# bt4_0_shield.net
KiCad netlist of a schematic drawn in EAGLE
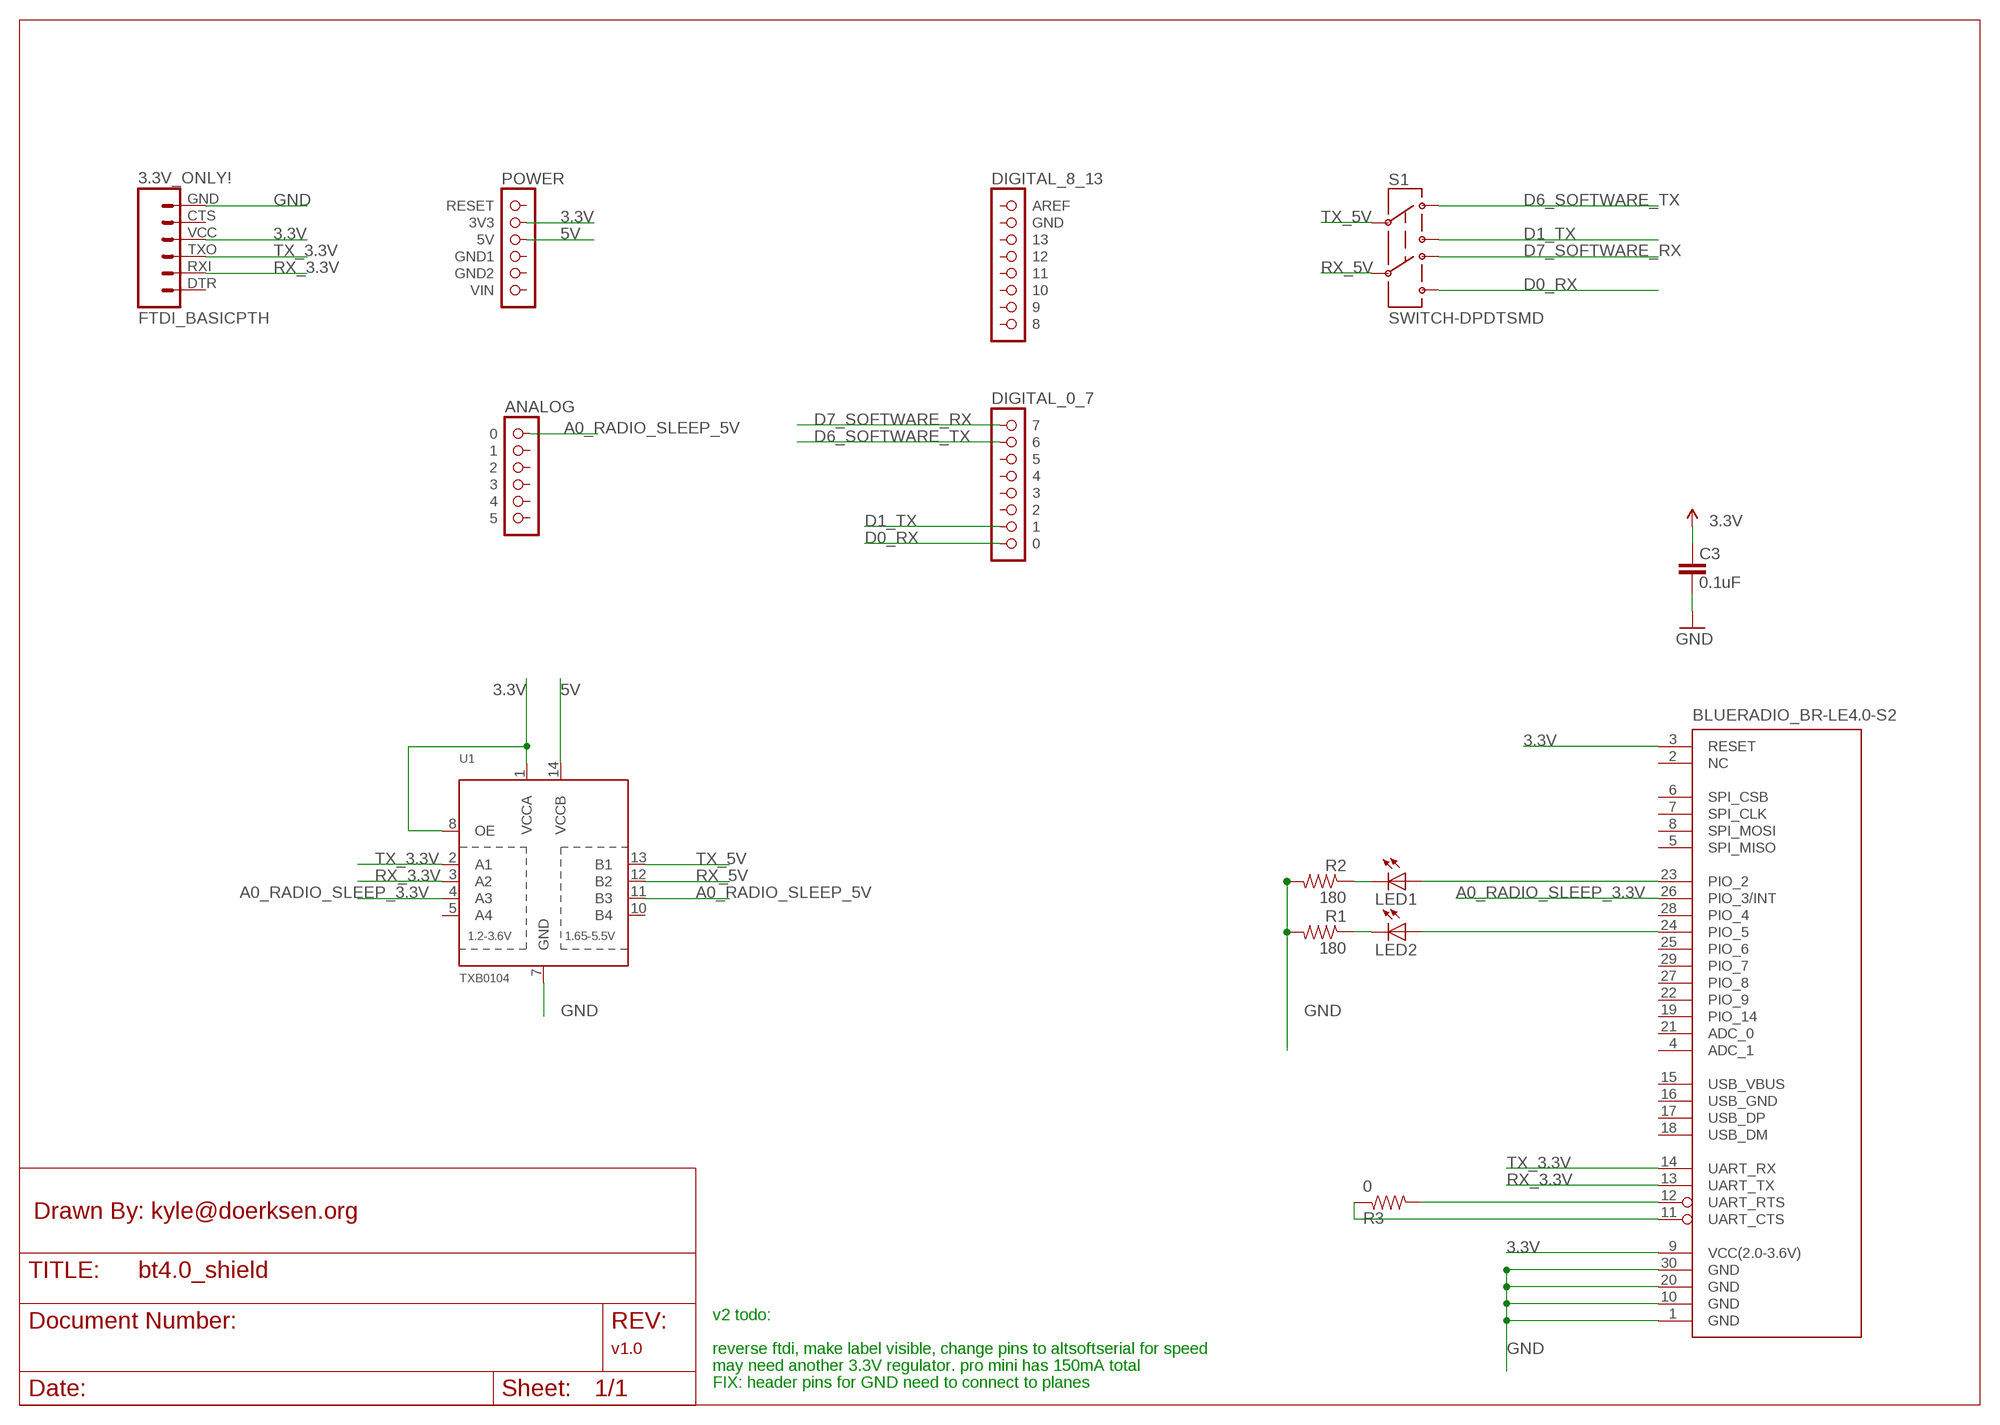
[diagram p0: schematic, sheet 1]

(export (version "E")
  (design (tool "Eeschema 10.0.6"))
  (components
    (comp (ref "3.3V_ONLY!")
      (value "FTDI_BASICPTH")
      (footprint "eagle-import:FTDI_BASIC")
      (libsource (lib "eagle-import") (part "FTDI_BASICPTH"))
    )
    (comp (ref "BLUERADIO_BR-LE4.0-S2")
      (value "BLUERADIO_BR-LE4.0-S2")
      (footprint "eagle-import:BLUERADIO_BR-LE4.0-S2")
      (libsource (lib "eagle-import") (part "BLUERADIO_BR-LE4.0-S2"))
    )
    (comp (ref "C3")
      (value "0.1uF")
      (footprint "eagle-import:0402-CAP")
      (libsource (lib "eagle-import") (part "CAP0402-CAP"))
    )
    (comp (ref "LED1")
      (value "LED0603")
      (footprint "eagle-import:LED-0603")
      (libsource (lib "eagle-import") (part "LED0603"))
    )
    (comp (ref "LED2")
      (value "LED0603")
      (footprint "eagle-import:LED-0603")
      (libsource (lib "eagle-import") (part "LED0603"))
    )
    (comp (ref "R1")
      (value "180")
      (footprint "eagle-import:0402-RES")
      (libsource (lib "eagle-import") (part "RESISTOR0402-RES"))
    )
    (comp (ref "R2")
      (value "180")
      (footprint "eagle-import:0402-RES")
      (libsource (lib "eagle-import") (part "RESISTOR0402-RES"))
    )
    (comp (ref "R3")
      (value "0")
      (footprint "eagle-import:0402-RES")
      (libsource (lib "eagle-import") (part "RESISTOR0402-RES"))
    )
    (comp (ref "S1")
      (value "SWITCH-DPDTSMD")
      (footprint "eagle-import:AYZ0202")
      (libsource (lib "eagle-import") (part "SWITCH-DPDTSMD"))
    )
    (comp (ref "U$1")
      (value "POWER")
      (footprint "eagle-import:1X06")
      (libsource (lib "eagle-import") (part "POWER"))
    )
    (comp (ref "U$2")
      (value "ANALOG")
      (footprint "eagle-import:1X06")
      (libsource (lib "eagle-import") (part "ANALOG"))
    )
    (comp (ref "U$3")
      (value "DIGITAL_0_7")
      (footprint "eagle-import:1X08")
      (libsource (lib "eagle-import") (part "DIGITAL_0_7"))
    )
    (comp (ref "U$4")
      (value "DIGITAL_8_13")
      (footprint "eagle-import:1X08")
      (libsource (lib "eagle-import") (part "DIGITAL_8_13"))
    )
    (comp (ref "U1")
      (value "TXB0104")
      (footprint "eagle-import:SO14")
      (libsource (lib "eagle-import") (part "TXB0104PWRSOIC14"))
    )
  )
  (nets
    (net (code "1") (name "/5V") (class "Default")
      (node (ref "U$1") (pin "3") (pinfunction "5V_3") (pintype "passive"))
      (node (ref "U1") (pin "14") (pinfunction "VCCB_14") (pintype "bidirectional"))
    )
    (net (code "2") (name "/A0_RADIO_SLEEP_3.3V") (class "Default")
      (node (ref "BLUERADIO_BR-LE4.0-S2") (pin "26") (pinfunction "PIO_3/INT_26") (pintype "bidirectional"))
      (node (ref "U1") (pin "4") (pinfunction "A3_4") (pintype "bidirectional"))
    )
    (net (code "3") (name "/A0_RADIO_SLEEP_5V") (class "Default")
      (node (ref "U$2") (pin "1") (pinfunction "0_1") (pintype "passive"))
      (node (ref "U1") (pin "11") (pinfunction "B3_11") (pintype "bidirectional"))
    )
    (net (code "4") (name "/D0_RX") (class "Default")
      (node (ref "S1") (pin "6") (pinfunction "6_6") (pintype "bidirectional"))
      (node (ref "U$3") (pin "8") (pinfunction "0_8") (pintype "passive"))
    )
    (net (code "5") (name "/D1_TX") (class "Default")
      (node (ref "S1") (pin "3") (pinfunction "3_3") (pintype "bidirectional"))
      (node (ref "U$3") (pin "7") (pinfunction "1_7") (pintype "passive"))
    )
    (net (code "6") (name "/D6_SOFTWARE_TX") (class "Default")
      (node (ref "S1") (pin "1") (pinfunction "1_1") (pintype "bidirectional"))
      (node (ref "U$3") (pin "2") (pinfunction "6_2") (pintype "passive"))
    )
    (net (code "7") (name "/D7_SOFTWARE_RX") (class "Default")
      (node (ref "S1") (pin "4") (pinfunction "4_4") (pintype "bidirectional"))
      (node (ref "U$3") (pin "1") (pinfunction "7_1") (pintype "passive"))
    )
    (net (code "8") (name "/RX_3.3V") (class "Default")
      (node (ref "3.3V_ONLY!") (pin "RXI") (pinfunction "2_RXI") (pintype "passive"))
      (node (ref "BLUERADIO_BR-LE4.0-S2") (pin "13") (pinfunction "UART_TX_13") (pintype "output"))
      (node (ref "U1") (pin "3") (pinfunction "A2_3") (pintype "bidirectional"))
    )
    (net (code "9") (name "/RX_5V") (class "Default")
      (node (ref "S1") (pin "5") (pinfunction "5_5") (pintype "bidirectional"))
      (node (ref "U1") (pin "12") (pinfunction "B2_12") (pintype "bidirectional"))
    )
    (net (code "10") (name "/TX_3.3V") (class "Default")
      (node (ref "3.3V_ONLY!") (pin "TXO") (pinfunction "3_TXO") (pintype "passive"))
      (node (ref "BLUERADIO_BR-LE4.0-S2") (pin "14") (pinfunction "UART_RX_14") (pintype "input"))
      (node (ref "U1") (pin "2") (pinfunction "A1_2") (pintype "bidirectional"))
    )
    (net (code "11") (name "/TX_5V") (class "Default")
      (node (ref "S1") (pin "2") (pinfunction "2_2") (pintype "bidirectional"))
      (node (ref "U1") (pin "13") (pinfunction "B1_13") (pintype "bidirectional"))
    )
    (net (code "12") (name "GND") (class "Default")
      (node (ref "3.3V_ONLY!") (pin "GND") (pinfunction "6_GND") (pintype "passive"))
      (node (ref "BLUERADIO_BR-LE4.0-S2") (pin "1") (pinfunction "GND_1") (pintype "power_in"))
      (node (ref "BLUERADIO_BR-LE4.0-S2") (pin "10") (pinfunction "GND_10") (pintype "power_in"))
      (node (ref "BLUERADIO_BR-LE4.0-S2") (pin "20") (pinfunction "GND_20") (pintype "power_in"))
      (node (ref "BLUERADIO_BR-LE4.0-S2") (pin "30") (pinfunction "GND_30") (pintype "power_in"))
      (node (ref "C3") (pin "1") (pinfunction "1_1") (pintype "passive"))
      (node (ref "R1") (pin "2") (pinfunction "2_2") (pintype "passive"))
      (node (ref "R2") (pin "2") (pinfunction "2_2") (pintype "passive"))
      (node (ref "U1") (pin "7") (pinfunction "GND_7") (pintype "bidirectional"))
    )
    (net (code "13") (name "Net-(BLUERADIO_BR-LE4.0-S2-PIO_2)") (class "Default")
      (node (ref "BLUERADIO_BR-LE4.0-S2") (pin "23") (pinfunction "PIO_2_23") (pintype "bidirectional"))
      (node (ref "LED1") (pin "A") (pinfunction "A_A") (pintype "passive"))
    )
    (net (code "14") (name "Net-(BLUERADIO_BR-LE4.0-S2-PIO_5)") (class "Default")
      (node (ref "BLUERADIO_BR-LE4.0-S2") (pin "24") (pinfunction "PIO_5_24") (pintype "bidirectional"))
      (node (ref "LED2") (pin "A") (pinfunction "A_A") (pintype "passive"))
    )
    (net (code "15") (name "Net-(BLUERADIO_BR-LE4.0-S2-UART_CTS)") (class "Default")
      (node (ref "BLUERADIO_BR-LE4.0-S2") (pin "11") (pinfunction "UART_CTS_11") (pintype "input"))
      (node (ref "R3") (pin "1") (pinfunction "1_1") (pintype "passive"))
    )
    (net (code "16") (name "Net-(BLUERADIO_BR-LE4.0-S2-UART_RTS)") (class "Default")
      (node (ref "BLUERADIO_BR-LE4.0-S2") (pin "12") (pinfunction "UART_RTS_12") (pintype "output"))
      (node (ref "R3") (pin "2") (pinfunction "2_2") (pintype "passive"))
    )
    (net (code "17") (name "Net-(LED1-PadC)") (class "Default")
      (node (ref "LED1") (pin "C") (pinfunction "C_C") (pintype "passive"))
      (node (ref "R2") (pin "1") (pinfunction "1_1") (pintype "passive"))
    )
    (net (code "18") (name "Net-(LED2-PadC)") (class "Default")
      (node (ref "LED2") (pin "C") (pinfunction "C_C") (pintype "passive"))
      (node (ref "R1") (pin "1") (pinfunction "1_1") (pintype "passive"))
    )
    (net (code "19") (name "VCC") (class "Default")
      (node (ref "3.3V_ONLY!") (pin "VCC") (pinfunction "4_VCC") (pintype "passive"))
      (node (ref "BLUERADIO_BR-LE4.0-S2") (pin "3") (pinfunction "RESET_3") (pintype "input"))
      (node (ref "BLUERADIO_BR-LE4.0-S2") (pin "9") (pinfunction "VCC(2.0-3.6V)_9") (pintype "power_in"))
      (node (ref "C3") (pin "2") (pinfunction "2_2") (pintype "passive"))
      (node (ref "U$1") (pin "2") (pinfunction "3V3_2") (pintype "passive"))
      (node (ref "U1") (pin "1") (pinfunction "VCCA_1") (pintype "bidirectional"))
      (node (ref "U1") (pin "8") (pinfunction "OE_8") (pintype "bidirectional"))
    )
    (net (code "20") (name "unconnected-(3.3V_ONLY!-1-PadDTR)") (class "Default")
      (node (ref "3.3V_ONLY!") (pin "DTR") (pinfunction "1_DTR") (pintype "passive"))
    )
    (net (code "21") (name "unconnected-(3.3V_ONLY!-5-PadCTS)") (class "Default")
      (node (ref "3.3V_ONLY!") (pin "CTS") (pinfunction "5_CTS") (pintype "passive"))
    )
    (net (code "22") (name "unconnected-(BLUERADIO_BR-LE4.0-S2-ADC_0-Pad21)") (class "Default")
      (node (ref "BLUERADIO_BR-LE4.0-S2") (pin "21") (pinfunction "ADC_0_21") (pintype "input"))
    )
    (net (code "23") (name "unconnected-(BLUERADIO_BR-LE4.0-S2-ADC_1-Pad4)") (class "Default")
      (node (ref "BLUERADIO_BR-LE4.0-S2") (pin "4") (pinfunction "ADC_1_4") (pintype "input"))
    )
    (net (code "24") (name "unconnected-(BLUERADIO_BR-LE4.0-S2-NC-Pad2)") (class "Default")
      (node (ref "BLUERADIO_BR-LE4.0-S2") (pin "2") (pinfunction "NC_2") (pintype "no_connect"))
    )
    (net (code "25") (name "unconnected-(BLUERADIO_BR-LE4.0-S2-PIO_4-Pad28)") (class "Default")
      (node (ref "BLUERADIO_BR-LE4.0-S2") (pin "28") (pinfunction "PIO_4_28") (pintype "bidirectional"))
    )
    (net (code "26") (name "unconnected-(BLUERADIO_BR-LE4.0-S2-PIO_6-Pad25)") (class "Default")
      (node (ref "BLUERADIO_BR-LE4.0-S2") (pin "25") (pinfunction "PIO_6_25") (pintype "bidirectional"))
    )
    (net (code "27") (name "unconnected-(BLUERADIO_BR-LE4.0-S2-PIO_7-Pad29)") (class "Default")
      (node (ref "BLUERADIO_BR-LE4.0-S2") (pin "29") (pinfunction "PIO_7_29") (pintype "bidirectional"))
    )
    (net (code "28") (name "unconnected-(BLUERADIO_BR-LE4.0-S2-PIO_8-Pad27)") (class "Default")
      (node (ref "BLUERADIO_BR-LE4.0-S2") (pin "27") (pinfunction "PIO_8_27") (pintype "bidirectional"))
    )
    (net (code "29") (name "unconnected-(BLUERADIO_BR-LE4.0-S2-PIO_9-Pad22)") (class "Default")
      (node (ref "BLUERADIO_BR-LE4.0-S2") (pin "22") (pinfunction "PIO_9_22") (pintype "bidirectional"))
    )
    (net (code "30") (name "unconnected-(BLUERADIO_BR-LE4.0-S2-PIO_14-Pad19)") (class "Default")
      (node (ref "BLUERADIO_BR-LE4.0-S2") (pin "19") (pinfunction "PIO_14_19") (pintype "bidirectional"))
    )
    (net (code "31") (name "unconnected-(BLUERADIO_BR-LE4.0-S2-SPI_CLK-Pad7)") (class "Default")
      (node (ref "BLUERADIO_BR-LE4.0-S2") (pin "7") (pinfunction "SPI_CLK_7") (pintype "bidirectional"))
    )
    (net (code "32") (name "unconnected-(BLUERADIO_BR-LE4.0-S2-SPI_CSB-Pad6)") (class "Default")
      (node (ref "BLUERADIO_BR-LE4.0-S2") (pin "6") (pinfunction "SPI_CSB_6") (pintype "bidirectional"))
    )
    (net (code "33") (name "unconnected-(BLUERADIO_BR-LE4.0-S2-SPI_MISO-Pad5)") (class "Default")
      (node (ref "BLUERADIO_BR-LE4.0-S2") (pin "5") (pinfunction "SPI_MISO_5") (pintype "bidirectional"))
    )
    (net (code "34") (name "unconnected-(BLUERADIO_BR-LE4.0-S2-SPI_MOSI-Pad8)") (class "Default")
      (node (ref "BLUERADIO_BR-LE4.0-S2") (pin "8") (pinfunction "SPI_MOSI_8") (pintype "bidirectional"))
    )
    (net (code "35") (name "unconnected-(BLUERADIO_BR-LE4.0-S2-USB_DM-Pad18)") (class "Default")
      (node (ref "BLUERADIO_BR-LE4.0-S2") (pin "18") (pinfunction "USB_DM_18") (pintype "bidirectional"))
    )
    (net (code "36") (name "unconnected-(BLUERADIO_BR-LE4.0-S2-USB_DP-Pad17)") (class "Default")
      (node (ref "BLUERADIO_BR-LE4.0-S2") (pin "17") (pinfunction "USB_DP_17") (pintype "bidirectional"))
    )
    (net (code "37") (name "unconnected-(BLUERADIO_BR-LE4.0-S2-USB_GND-Pad16)") (class "Default")
      (node (ref "BLUERADIO_BR-LE4.0-S2") (pin "16") (pinfunction "USB_GND_16") (pintype "bidirectional"))
    )
    (net (code "38") (name "unconnected-(BLUERADIO_BR-LE4.0-S2-USB_VBUS-Pad15)") (class "Default")
      (node (ref "BLUERADIO_BR-LE4.0-S2") (pin "15") (pinfunction "USB_VBUS_15") (pintype "bidirectional"))
    )
    (net (code "39") (name "unconnected-(U$1-GND1-Pad4)") (class "Default")
      (node (ref "U$1") (pin "4") (pinfunction "GND1_4") (pintype "passive"))
    )
    (net (code "40") (name "unconnected-(U$1-GND2-Pad5)") (class "Default")
      (node (ref "U$1") (pin "5") (pinfunction "GND2_5") (pintype "passive"))
    )
    (net (code "41") (name "unconnected-(U$1-RESET-Pad1)") (class "Default")
      (node (ref "U$1") (pin "1") (pinfunction "RESET_1") (pintype "passive"))
    )
    (net (code "42") (name "unconnected-(U$1-VIN-Pad6)") (class "Default")
      (node (ref "U$1") (pin "6") (pinfunction "VIN_6") (pintype "passive"))
    )
    (net (code "43") (name "unconnected-(U$2-1-Pad2)") (class "Default")
      (node (ref "U$2") (pin "2") (pinfunction "1_2") (pintype "passive"))
    )
    (net (code "44") (name "unconnected-(U$2-2-Pad3)") (class "Default")
      (node (ref "U$2") (pin "3") (pinfunction "2_3") (pintype "passive"))
    )
    (net (code "45") (name "unconnected-(U$2-3-Pad4)") (class "Default")
      (node (ref "U$2") (pin "4") (pinfunction "3_4") (pintype "passive"))
    )
    (net (code "46") (name "unconnected-(U$2-4-Pad5)") (class "Default")
      (node (ref "U$2") (pin "5") (pinfunction "4_5") (pintype "passive"))
    )
    (net (code "47") (name "unconnected-(U$2-5-Pad6)") (class "Default")
      (node (ref "U$2") (pin "6") (pinfunction "5_6") (pintype "passive"))
    )
    (net (code "48") (name "unconnected-(U$3-2-Pad6)") (class "Default")
      (node (ref "U$3") (pin "6") (pinfunction "2_6") (pintype "passive"))
    )
    (net (code "49") (name "unconnected-(U$3-3-Pad5)") (class "Default")
      (node (ref "U$3") (pin "5") (pinfunction "3_5") (pintype "passive"))
    )
    (net (code "50") (name "unconnected-(U$3-5-Pad3)") (class "Default")
      (node (ref "U$3") (pin "3") (pinfunction "5_3") (pintype "passive"))
    )
    (net (code "51") (name "unconnected-(U$3-Pad4)") (class "Default")
      (node (ref "U$3") (pin "4") (pinfunction "4_4") (pintype "passive"))
    )
    (net (code "52") (name "unconnected-(U$4-9-Pad7)") (class "Default")
      (node (ref "U$4") (pin "7") (pinfunction "9_7") (pintype "passive"))
    )
    (net (code "53") (name "unconnected-(U$4-10-Pad6)") (class "Default")
      (node (ref "U$4") (pin "6") (pinfunction "10_6") (pintype "passive"))
    )
    (net (code "54") (name "unconnected-(U$4-11-Pad5)") (class "Default")
      (node (ref "U$4") (pin "5") (pinfunction "11_5") (pintype "passive"))
    )
    (net (code "55") (name "unconnected-(U$4-12-Pad4)") (class "Default")
      (node (ref "U$4") (pin "4") (pinfunction "12_4") (pintype "passive"))
    )
    (net (code "56") (name "unconnected-(U$4-13-Pad3)") (class "Default")
      (node (ref "U$4") (pin "3") (pinfunction "13_3") (pintype "passive"))
    )
    (net (code "57") (name "unconnected-(U$4-AREF-Pad1)") (class "Default")
      (node (ref "U$4") (pin "1") (pinfunction "AREF_1") (pintype "passive"))
    )
    (net (code "58") (name "unconnected-(U$4-GND-Pad2)") (class "Default")
      (node (ref "U$4") (pin "2") (pinfunction "GND_2") (pintype "passive"))
    )
    (net (code "59") (name "unconnected-(U$4-Pad8)") (class "Default")
      (node (ref "U$4") (pin "8") (pinfunction "8_8") (pintype "passive"))
    )
    (net (code "60") (name "unconnected-(U1-A4-Pad5)") (class "Default")
      (node (ref "U1") (pin "5") (pinfunction "A4_5") (pintype "bidirectional"))
    )
    (net (code "61") (name "unconnected-(U1-B4-Pad10)") (class "Default")
      (node (ref "U1") (pin "10") (pinfunction "B4_10") (pintype "bidirectional"))
    )
  )
)
